# SECUREBRD_003.net
KiCad netlist of a schematic drawn in EAGLE
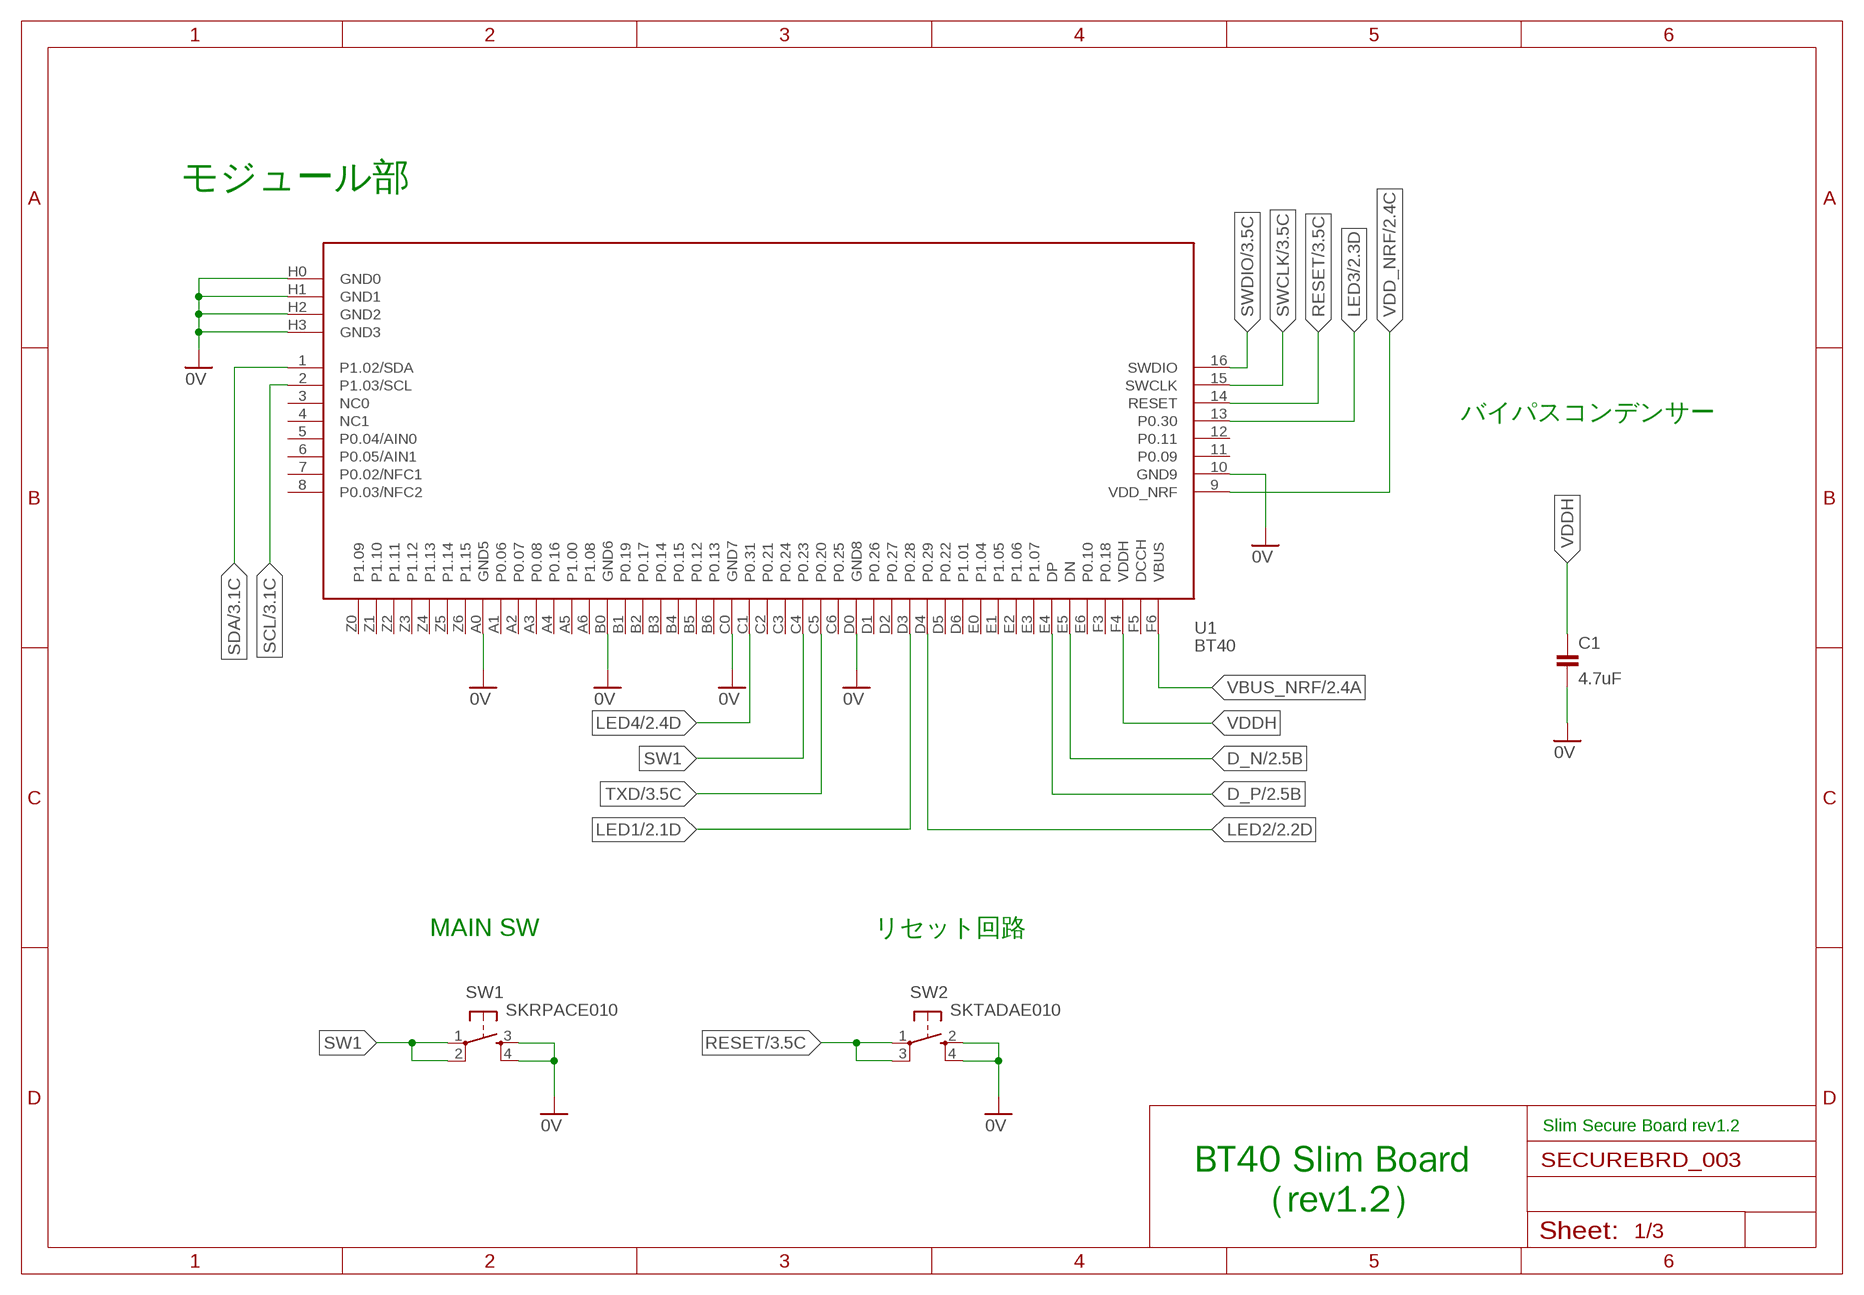
[diagram p0: schematic, sheet 1]
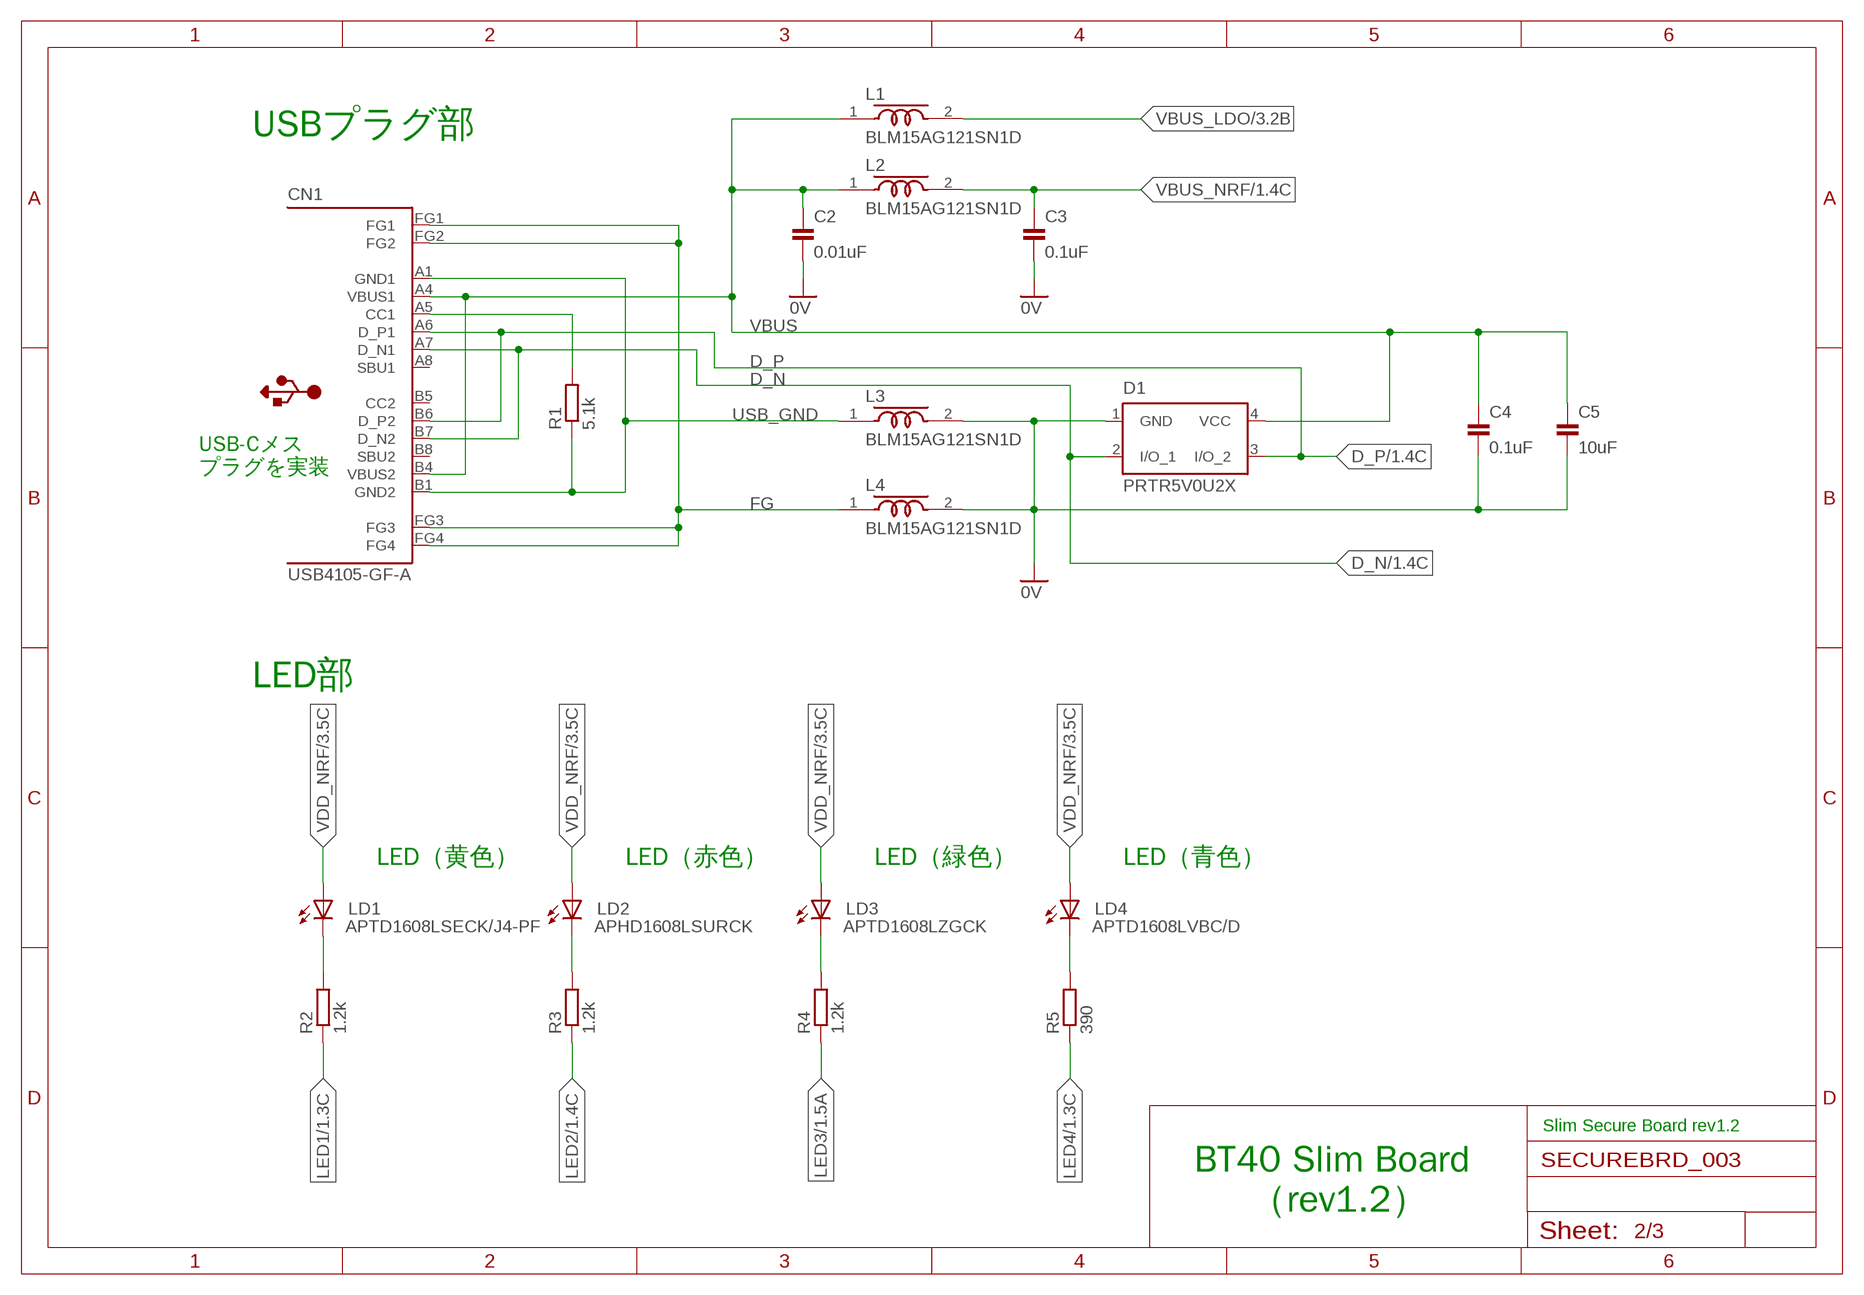
[diagram p1: schematic, sheet 2]
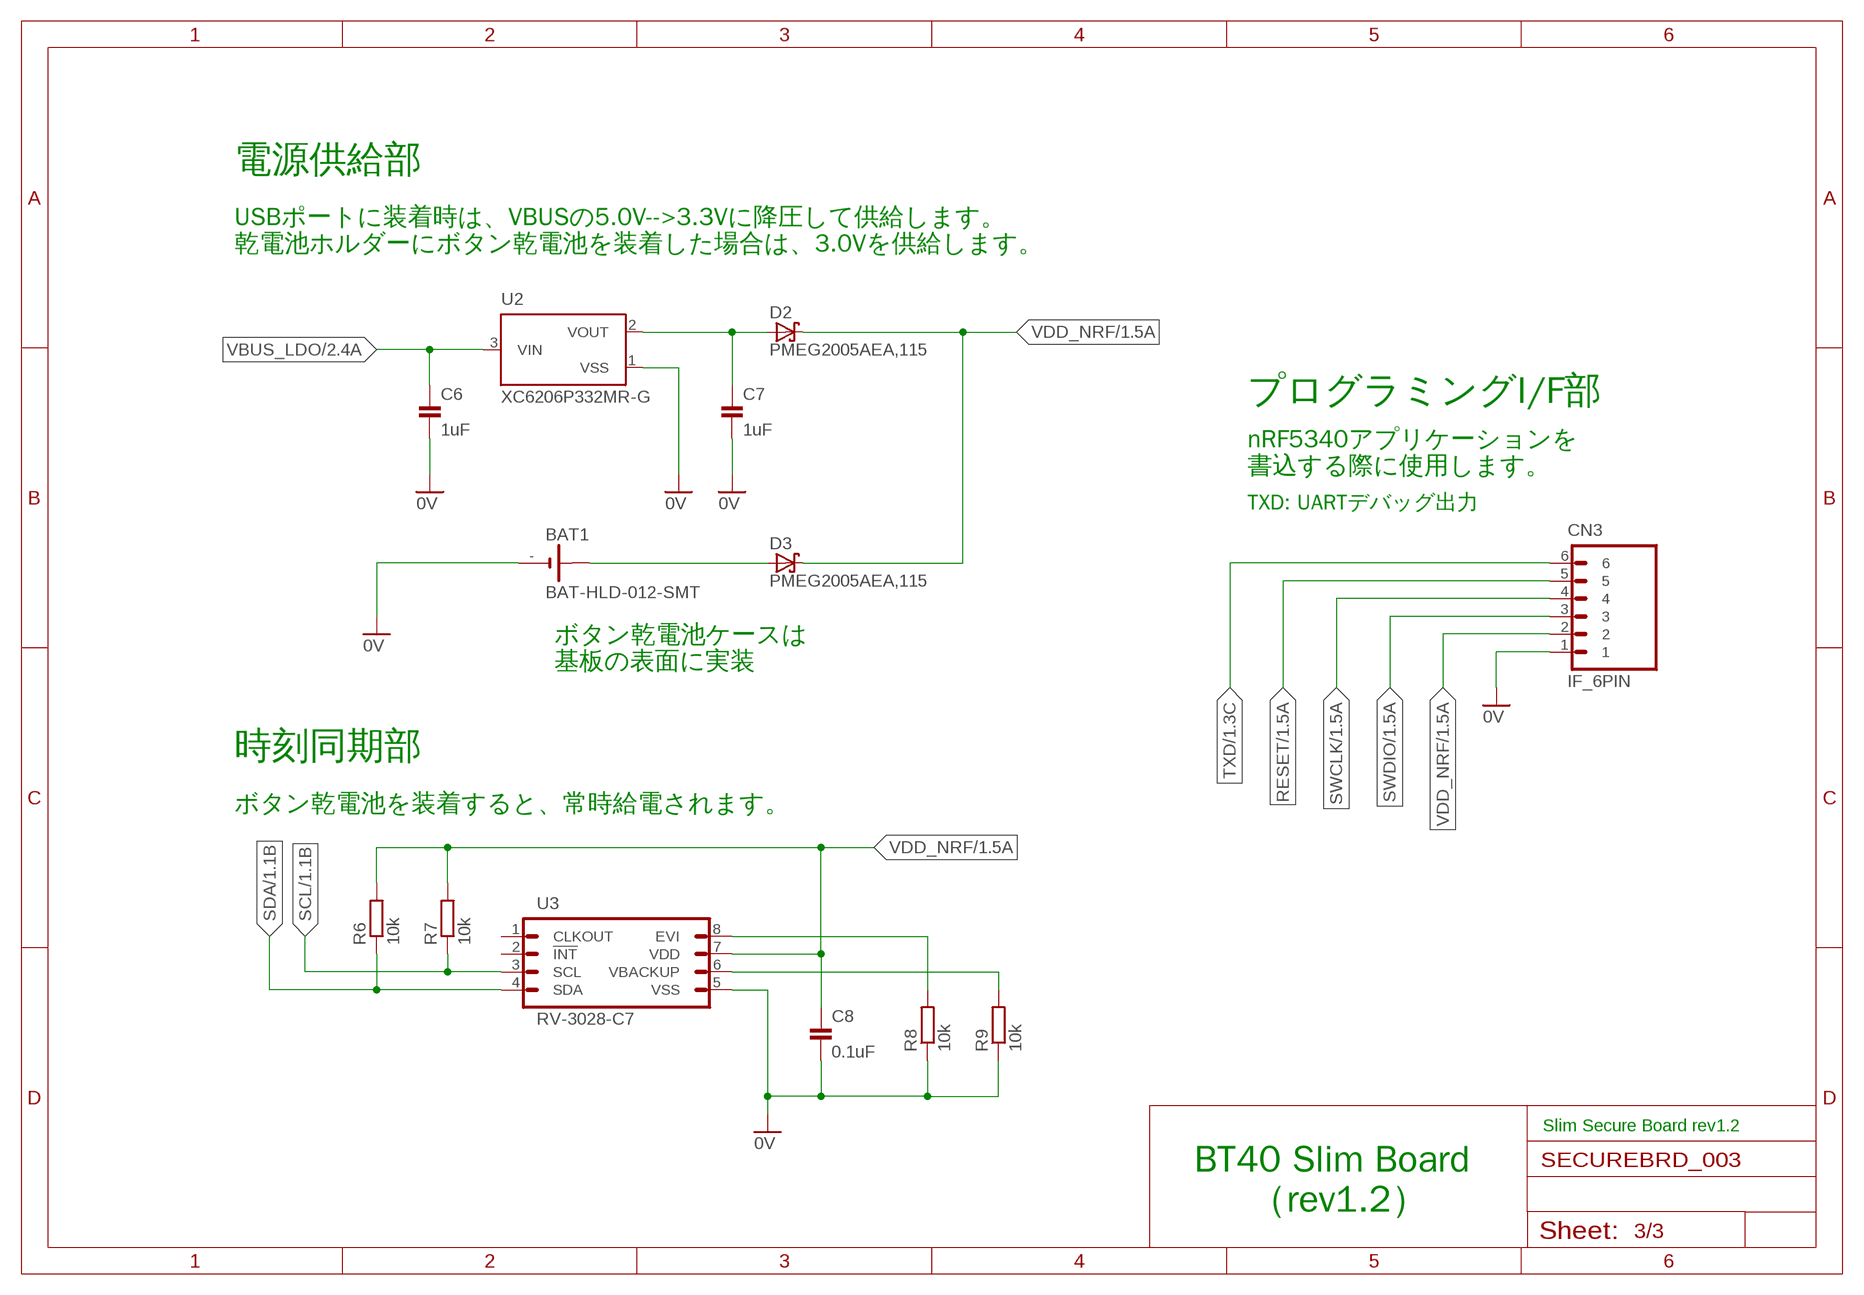
[diagram p2: schematic, sheet 3]

(export (version "E")
  (design (tool "Eeschema 10.0.6"))
  (components
    (comp (ref "BAT1")
      (value "BAT-HLD-012-SMT")
      (footprint "eagle-import:BAT-HLD-012-SMT")
      (libsource (lib "eagle-import") (part "BAT-HLD-012-SMT"))
    )
    (comp (ref "C6")
      (value "1uF")
      (footprint "eagle-import:C0603K")
      (libsource (lib "eagle-import") (part "CAP_0603"))
    )
    (comp (ref "C7")
      (value "1uF")
      (footprint "eagle-import:C0603K")
      (libsource (lib "eagle-import") (part "CAP_0603"))
    )
    (comp (ref "C8")
      (value "0.1uF")
      (footprint "eagle-import:C0402K")
      (libsource (lib "eagle-import") (part "CAP_0402K"))
    )
    (comp (ref "CN3")
      (value "IF_6PIN")
      (footprint "eagle-import:HEADER_6PIN")
      (libsource (lib "eagle-import") (part "IF_6PIN"))
    )
    (comp (ref "D2")
      (value "PMEG2005AEA,115")
      (footprint "eagle-import:SOD323-W")
      (libsource (lib "eagle-import") (part "PMEG2005AEA,115"))
    )
    (comp (ref "D3")
      (value "PMEG2005AEA,115")
      (footprint "eagle-import:SOD323-W")
      (libsource (lib "eagle-import") (part "PMEG2005AEA,115"))
    )
    (comp (ref "R6")
      (value "10k")
      (footprint "eagle-import:R0402")
      (libsource (lib "eagle-import") (part "RESISTOR_0402"))
    )
    (comp (ref "R7")
      (value "10k")
      (footprint "eagle-import:R0402")
      (libsource (lib "eagle-import") (part "RESISTOR_0402"))
    )
    (comp (ref "R8")
      (value "10k")
      (footprint "eagle-import:R0402")
      (libsource (lib "eagle-import") (part "RESISTOR_0402"))
    )
    (comp (ref "R9")
      (value "10k")
      (footprint "eagle-import:R0402")
      (libsource (lib "eagle-import") (part "RESISTOR_0402"))
    )
    (comp (ref "U2")
      (value "XC6206P332MR-G")
      (footprint "eagle-import:SOT23")
      (libsource (lib "eagle-import") (part "XC6206P332MR-G"))
    )
    (comp (ref "U3")
      (value "RV-3028-C7")
      (footprint "eagle-import:SON-8")
      (libsource (lib "eagle-import") (part "RV-3028-C7"))
    )
    (comp (ref "C2")
      (value "0.01uF")
      (footprint "eagle-import:C0402K")
      (libsource (lib "eagle-import") (part "CAP_0402K"))
    )
    (comp (ref "C3")
      (value "0.1uF")
      (footprint "eagle-import:C0402K")
      (libsource (lib "eagle-import") (part "CAP_0402K"))
    )
    (comp (ref "C4")
      (value "0.1uF")
      (footprint "eagle-import:C0402K")
      (libsource (lib "eagle-import") (part "CAP_0402K"))
    )
    (comp (ref "C5")
      (value "10uF")
      (footprint "eagle-import:C0603K")
      (libsource (lib "eagle-import") (part "CAP_0603"))
    )
    (comp (ref "CN1")
      (value "USB4105-GF-A")
      (footprint "eagle-import:USB4105-GF-A")
      (libsource (lib "eagle-import") (part "USB4105-GF-A"))
    )
    (comp (ref "D1")
      (value "PRTR5V0U2X")
      (footprint "eagle-import:SOT143B")
      (libsource (lib "eagle-import") (part "PRTR5V0U2X"))
    )
    (comp (ref "L1")
      (value "BLM15AG121SN1D")
      (footprint "eagle-import:C0402K")
      (libsource (lib "eagle-import") (part "BLM15AG121SN1D"))
    )
    (comp (ref "L2")
      (value "BLM15AG121SN1D")
      (footprint "eagle-import:C0402K")
      (libsource (lib "eagle-import") (part "BLM15AG121SN1D"))
    )
    (comp (ref "L3")
      (value "BLM15AG121SN1D")
      (footprint "eagle-import:C0402K")
      (libsource (lib "eagle-import") (part "BLM15AG121SN1D"))
    )
    (comp (ref "L4")
      (value "BLM15AG121SN1D")
      (footprint "eagle-import:C0402K")
      (libsource (lib "eagle-import") (part "BLM15AG121SN1D"))
    )
    (comp (ref "LD1")
      (value "APTD1608LSECK/J4-PF")
      (footprint "eagle-import:APTD1608")
      (libsource (lib "eagle-import") (part "APTD1608LSECK/J4-PF"))
    )
    (comp (ref "LD2")
      (value "APHD1608LSURCK")
      (footprint "eagle-import:APTD1608")
      (libsource (lib "eagle-import") (part "APHD1608LSURCK"))
    )
    (comp (ref "LD3")
      (value "APTD1608LZGCK")
      (footprint "eagle-import:APTD1608")
      (libsource (lib "eagle-import") (part "APTD1608LZGCK"))
    )
    (comp (ref "LD4")
      (value "APTD1608LVBC/D")
      (footprint "eagle-import:APTD1608")
      (libsource (lib "eagle-import") (part "APTD1608LVBC/D"))
    )
    (comp (ref "R1")
      (value "5.1k")
      (footprint "eagle-import:R0402")
      (libsource (lib "eagle-import") (part "RESISTOR_0402"))
    )
    (comp (ref "R2")
      (value "1.2k")
      (footprint "eagle-import:R0402")
      (libsource (lib "eagle-import") (part "RESISTOR_0402"))
    )
    (comp (ref "R3")
      (value "1.2k")
      (footprint "eagle-import:R0402")
      (libsource (lib "eagle-import") (part "RESISTOR_0402"))
    )
    (comp (ref "R4")
      (value "1.2k")
      (footprint "eagle-import:R0402")
      (libsource (lib "eagle-import") (part "RESISTOR_0402"))
    )
    (comp (ref "R5")
      (value "390")
      (footprint "eagle-import:R0402")
      (libsource (lib "eagle-import") (part "RESISTOR_0402"))
    )
    (comp (ref "C1")
      (value "4.7uF")
      (footprint "eagle-import:C0603K")
      (libsource (lib "eagle-import") (part "CAP_0603"))
    )
    (comp (ref "SW1")
      (value "SKRPACE010")
      (footprint "eagle-import:SKRPACE010")
      (libsource (lib "eagle-import") (part "SKRPACE010"))
    )
    (comp (ref "SW2")
      (value "SKTADAE010")
      (footprint "eagle-import:SKTADAE010")
      (libsource (lib "eagle-import") (part "SKTADAE010"))
    )
    (comp (ref "U1")
      (value "BT40")
      (footprint "eagle-import:BM40-B_1PRIMARY")
      (libsource (lib "eagle-import") (part "BT40"))
    )
  )
  (nets
    (net (code "1") (name "0V") (class "Default")
      (node (ref "BAT1") (pin "-") (pinfunction "-_-") (pintype "passive"))
      (node (ref "C1") (pin "2") (pinfunction "2_2") (pintype "passive"))
      (node (ref "C2") (pin "2") (pinfunction "2_2") (pintype "passive"))
      (node (ref "C3") (pin "2") (pinfunction "2_2") (pintype "passive"))
      (node (ref "C4") (pin "2") (pinfunction "2_2") (pintype "passive"))
      (node (ref "C5") (pin "2") (pinfunction "2_2") (pintype "passive"))
      (node (ref "C6") (pin "2") (pinfunction "2_2") (pintype "passive"))
      (node (ref "C7") (pin "2") (pinfunction "2_2") (pintype "passive"))
      (node (ref "C8") (pin "2") (pinfunction "2_2") (pintype "passive"))
      (node (ref "CN3") (pin "1") (pinfunction "1_1") (pintype "passive"))
      (node (ref "D1") (pin "1") (pinfunction "GND_1") (pintype "passive"))
      (node (ref "L3") (pin "2") (pinfunction "2_2") (pintype "passive"))
      (node (ref "L4") (pin "2") (pinfunction "2_2") (pintype "passive"))
      (node (ref "R8") (pin "1") (pinfunction "1_1") (pintype "passive"))
      (node (ref "R9") (pin "1") (pinfunction "1_1") (pintype "passive"))
      (node (ref "SW1") (pin "3") (pinfunction "S_3") (pintype "passive"))
      (node (ref "SW1") (pin "4") (pinfunction "S1_4") (pintype "passive"))
      (node (ref "SW2") (pin "2") (pinfunction "S_2") (pintype "passive"))
      (node (ref "SW2") (pin "4") (pinfunction "S1_4") (pintype "passive"))
      (node (ref "U1") (pin "10") (pinfunction "GND9_10") (pintype "passive"))
      (node (ref "U1") (pin "A0") (pinfunction "GND5_A0") (pintype "passive"))
      (node (ref "U1") (pin "B0") (pinfunction "GND6_B0") (pintype "passive"))
      (node (ref "U1") (pin "C0") (pinfunction "GND7_C0") (pintype "passive"))
      (node (ref "U1") (pin "D0") (pinfunction "GND8_D0") (pintype "passive"))
      (node (ref "U1") (pin "H0") (pinfunction "GND0_H0") (pintype "passive"))
      (node (ref "U1") (pin "H1") (pinfunction "GND1_H1") (pintype "passive"))
      (node (ref "U1") (pin "H2") (pinfunction "GND2_H2") (pintype "passive"))
      (node (ref "U1") (pin "H3") (pinfunction "GND3_H3") (pintype "passive"))
      (node (ref "U2") (pin "1") (pinfunction "VSS_1") (pintype "passive"))
      (node (ref "U3") (pin "5") (pinfunction "VSS_5") (pintype "passive"))
    )
    (net (code "2") (name "D_N") (class "Default")
      (node (ref "CN1") (pin "A7") (pinfunction "D_N1_A7") (pintype "bidirectional"))
      (node (ref "CN1") (pin "B7") (pinfunction "D_N2_B7") (pintype "bidirectional"))
      (node (ref "D1") (pin "2") (pinfunction "I/O_1_2") (pintype "bidirectional"))
      (node (ref "U1") (pin "E5") (pinfunction "DN_E5") (pintype "bidirectional"))
    )
    (net (code "3") (name "D_P") (class "Default")
      (node (ref "CN1") (pin "A6") (pinfunction "D_P1_A6") (pintype "bidirectional"))
      (node (ref "CN1") (pin "B6") (pinfunction "D_P2_B6") (pintype "bidirectional"))
      (node (ref "D1") (pin "3") (pinfunction "I/O_2_3") (pintype "bidirectional"))
      (node (ref "U1") (pin "E4") (pinfunction "DP_E4") (pintype "bidirectional"))
    )
    (net (code "4") (name "FG") (class "Default")
      (node (ref "CN1") (pin "FG1") (pinfunction "FG1_FG1") (pintype "passive"))
      (node (ref "CN1") (pin "FG2") (pinfunction "FG2_FG2") (pintype "bidirectional"))
      (node (ref "CN1") (pin "FG3") (pinfunction "FG3_FG3") (pintype "passive"))
      (node (ref "CN1") (pin "FG4") (pinfunction "FG4_FG4") (pintype "passive"))
      (node (ref "L4") (pin "1") (pinfunction "1_1") (pintype "passive"))
    )
    (net (code "5") (name "LED1") (class "Default")
      (node (ref "R2") (pin "1") (pinfunction "1_1") (pintype "passive"))
      (node (ref "U1") (pin "D3") (pinfunction "P0.28_D3") (pintype "bidirectional"))
    )
    (net (code "6") (name "LED2") (class "Default")
      (node (ref "R3") (pin "1") (pinfunction "1_1") (pintype "passive"))
      (node (ref "U1") (pin "D4") (pinfunction "P0.29_D4") (pintype "bidirectional"))
    )
    (net (code "7") (name "LED3") (class "Default")
      (node (ref "R4") (pin "1") (pinfunction "1_1") (pintype "passive"))
      (node (ref "U1") (pin "13") (pinfunction "P0.30_13") (pintype "bidirectional"))
    )
    (net (code "8") (name "LED4") (class "Default")
      (node (ref "R5") (pin "1") (pinfunction "1_1") (pintype "passive"))
      (node (ref "U1") (pin "C1") (pinfunction "P0.31_C1") (pintype "bidirectional"))
    )
    (net (code "9") (name "Net-(BAT1-+)") (class "Default")
      (node (ref "BAT1") (pin "+@2") (pinfunction "+_+@2") (pintype "passive"))
      (node (ref "D3") (pin "A") (pinfunction "A_A") (pintype "passive"))
    )
    (net (code "10") (name "Net-(CN1-CC1)") (class "Default")
      (node (ref "CN1") (pin "A5") (pinfunction "CC1_A5") (pintype "passive"))
      (node (ref "R1") (pin "2") (pinfunction "2_2") (pintype "passive"))
    )
    (net (code "11") (name "Net-(LD1-PadC)") (class "Default")
      (node (ref "LD1") (pin "C") (pinfunction "C_C") (pintype "passive"))
      (node (ref "R2") (pin "2") (pinfunction "2_2") (pintype "passive"))
    )
    (net (code "12") (name "Net-(LD2-PadC)") (class "Default")
      (node (ref "LD2") (pin "C") (pinfunction "C_C") (pintype "passive"))
      (node (ref "R3") (pin "2") (pinfunction "2_2") (pintype "passive"))
    )
    (net (code "13") (name "Net-(LD3-PadC)") (class "Default")
      (node (ref "LD3") (pin "C") (pinfunction "C_C") (pintype "passive"))
      (node (ref "R4") (pin "2") (pinfunction "2_2") (pintype "passive"))
    )
    (net (code "14") (name "Net-(LD4-PadC)") (class "Default")
      (node (ref "LD4") (pin "C") (pinfunction "C_C") (pintype "passive"))
      (node (ref "R5") (pin "2") (pinfunction "2_2") (pintype "passive"))
    )
    (net (code "15") (name "Net-(U2-VOUT)") (class "Default")
      (node (ref "C7") (pin "1") (pinfunction "1_1") (pintype "passive"))
      (node (ref "D2") (pin "A") (pinfunction "A_A") (pintype "passive"))
      (node (ref "U2") (pin "2") (pinfunction "VOUT_2") (pintype "passive"))
    )
    (net (code "16") (name "Net-(U3-EVI)") (class "Default")
      (node (ref "R8") (pin "2") (pinfunction "2_2") (pintype "passive"))
      (node (ref "U3") (pin "8") (pinfunction "EVI_8") (pintype "bidirectional"))
    )
    (net (code "17") (name "Net-(U3-VBACKUP)") (class "Default")
      (node (ref "R9") (pin "2") (pinfunction "2_2") (pintype "passive"))
      (node (ref "U3") (pin "6") (pinfunction "VBACKUP_6") (pintype "passive"))
    )
    (net (code "18") (name "RESET") (class "Default")
      (node (ref "CN3") (pin "5") (pinfunction "5_5") (pintype "passive"))
      (node (ref "SW2") (pin "1") (pinfunction "P_1") (pintype "passive"))
      (node (ref "SW2") (pin "3") (pinfunction "P1_3") (pintype "passive"))
      (node (ref "U1") (pin "14") (pinfunction "RESET_14") (pintype "bidirectional"))
    )
    (net (code "19") (name "SCL") (class "Default")
      (node (ref "R7") (pin "1") (pinfunction "1_1") (pintype "passive"))
      (node (ref "U1") (pin "2") (pinfunction "P1.03/SCL_2") (pintype "bidirectional"))
      (node (ref "U3") (pin "3") (pinfunction "SCL_3") (pintype "bidirectional"))
    )
    (net (code "20") (name "SDA") (class "Default")
      (node (ref "R6") (pin "1") (pinfunction "1_1") (pintype "passive"))
      (node (ref "U1") (pin "1") (pinfunction "P1.02/SDA_1") (pintype "bidirectional"))
      (node (ref "U3") (pin "4") (pinfunction "SDA_4") (pintype "bidirectional"))
    )
    (net (code "21") (name "SW1") (class "Default")
      (node (ref "SW1") (pin "1") (pinfunction "P_1") (pintype "passive"))
      (node (ref "SW1") (pin "2") (pinfunction "P1_2") (pintype "passive"))
      (node (ref "U1") (pin "C4") (pinfunction "P0.23_C4") (pintype "bidirectional"))
    )
    (net (code "22") (name "SWCLK") (class "Default")
      (node (ref "CN3") (pin "4") (pinfunction "4_4") (pintype "passive"))
      (node (ref "U1") (pin "15") (pinfunction "SWCLK_15") (pintype "bidirectional"))
    )
    (net (code "23") (name "SWDIO") (class "Default")
      (node (ref "CN3") (pin "3") (pinfunction "3_3") (pintype "passive"))
      (node (ref "U1") (pin "16") (pinfunction "SWDIO_16") (pintype "bidirectional"))
    )
    (net (code "24") (name "TXD") (class "Default")
      (node (ref "CN3") (pin "6") (pinfunction "6_6") (pintype "passive"))
      (node (ref "U1") (pin "C5") (pinfunction "P0.20_C5") (pintype "bidirectional"))
    )
    (net (code "25") (name "USB_GND") (class "Default")
      (node (ref "CN1") (pin "A1") (pinfunction "GND1_A1") (pintype "passive"))
      (node (ref "CN1") (pin "B1") (pinfunction "GND2_B1") (pintype "passive"))
      (node (ref "L3") (pin "1") (pinfunction "1_1") (pintype "passive"))
      (node (ref "R1") (pin "1") (pinfunction "1_1") (pintype "passive"))
    )
    (net (code "26") (name "VBUS") (class "Default")
      (node (ref "C2") (pin "1") (pinfunction "1_1") (pintype "passive"))
      (node (ref "C4") (pin "1") (pinfunction "1_1") (pintype "passive"))
      (node (ref "C5") (pin "1") (pinfunction "1_1") (pintype "passive"))
      (node (ref "CN1") (pin "A4") (pinfunction "VBUS1_A4") (pintype "passive"))
      (node (ref "CN1") (pin "B4") (pinfunction "VBUS2_B4") (pintype "passive"))
      (node (ref "D1") (pin "4") (pinfunction "VCC_4") (pintype "passive"))
      (node (ref "L1") (pin "1") (pinfunction "1_1") (pintype "passive"))
      (node (ref "L2") (pin "1") (pinfunction "1_1") (pintype "passive"))
    )
    (net (code "27") (name "VBUS_LDO") (class "Default")
      (node (ref "C6") (pin "1") (pinfunction "1_1") (pintype "passive"))
      (node (ref "L1") (pin "2") (pinfunction "2_2") (pintype "passive"))
      (node (ref "U2") (pin "3") (pinfunction "VIN_3") (pintype "passive"))
    )
    (net (code "28") (name "VBUS_NRF") (class "Default")
      (node (ref "C3") (pin "1") (pinfunction "1_1") (pintype "passive"))
      (node (ref "L2") (pin "2") (pinfunction "2_2") (pintype "passive"))
      (node (ref "U1") (pin "F6") (pinfunction "VBUS_F6") (pintype "passive"))
    )
    (net (code "29") (name "VDDH") (class "Default")
      (node (ref "C1") (pin "1") (pinfunction "1_1") (pintype "passive"))
      (node (ref "U1") (pin "F4") (pinfunction "VDDH_F4") (pintype "passive"))
    )
    (net (code "30") (name "VDD_NRF") (class "Default")
      (node (ref "C8") (pin "1") (pinfunction "1_1") (pintype "passive"))
      (node (ref "CN3") (pin "2") (pinfunction "2_2") (pintype "passive"))
      (node (ref "D2") (pin "C") (pinfunction "C_C") (pintype "passive"))
      (node (ref "D3") (pin "C") (pinfunction "C_C") (pintype "passive"))
      (node (ref "LD1") (pin "A") (pinfunction "A_A") (pintype "passive"))
      (node (ref "LD2") (pin "A") (pinfunction "A_A") (pintype "passive"))
      (node (ref "LD3") (pin "A") (pinfunction "A_A") (pintype "passive"))
      (node (ref "LD4") (pin "A") (pinfunction "A_A") (pintype "passive"))
      (node (ref "R6") (pin "2") (pinfunction "2_2") (pintype "passive"))
      (node (ref "R7") (pin "2") (pinfunction "2_2") (pintype "passive"))
      (node (ref "U1") (pin "9") (pinfunction "VDD_NRF_9") (pintype "passive"))
      (node (ref "U3") (pin "7") (pinfunction "VDD_7") (pintype "passive"))
    )
    (net (code "31") (name "unconnected-(CN1-CC2-PadB5)") (class "Default")
      (node (ref "CN1") (pin "B5") (pinfunction "CC2_B5") (pintype "passive"))
    )
    (net (code "32") (name "unconnected-(CN1-SBU1-PadA8)") (class "Default")
      (node (ref "CN1") (pin "A8") (pinfunction "SBU1_A8") (pintype "passive"))
    )
    (net (code "33") (name "unconnected-(CN1-SBU2-PadB8)") (class "Default")
      (node (ref "CN1") (pin "B8") (pinfunction "SBU2_B8") (pintype "passive"))
    )
    (net (code "34") (name "unconnected-(U1-DCCH-PadF5)") (class "Default")
      (node (ref "U1") (pin "F5") (pinfunction "DCCH_F5") (pintype "passive"))
    )
    (net (code "35") (name "unconnected-(U1-NC0-Pad3)") (class "Default")
      (node (ref "U1") (pin "3") (pinfunction "NC0_3") (pintype "no_connect"))
    )
    (net (code "36") (name "unconnected-(U1-NC1-Pad4)") (class "Default")
      (node (ref "U1") (pin "4") (pinfunction "NC1_4") (pintype "no_connect"))
    )
    (net (code "37") (name "unconnected-(U1-P0.02{slash}NFC1-Pad7)") (class "Default")
      (node (ref "U1") (pin "7") (pinfunction "P0.02/NFC1_7") (pintype "bidirectional"))
    )
    (net (code "38") (name "unconnected-(U1-P0.03{slash}NFC2-Pad8)") (class "Default")
      (node (ref "U1") (pin "8") (pinfunction "P0.03/NFC2_8") (pintype "bidirectional"))
    )
    (net (code "39") (name "unconnected-(U1-P0.04{slash}AIN0-Pad5)") (class "Default")
      (node (ref "U1") (pin "5") (pinfunction "P0.04/AIN0_5") (pintype "bidirectional"))
    )
    (net (code "40") (name "unconnected-(U1-P0.05{slash}AIN1-Pad6)") (class "Default")
      (node (ref "U1") (pin "6") (pinfunction "P0.05/AIN1_6") (pintype "bidirectional"))
    )
    (net (code "41") (name "unconnected-(U1-P0.06-PadA1)") (class "Default")
      (node (ref "U1") (pin "A1") (pinfunction "P0.06_A1") (pintype "bidirectional"))
    )
    (net (code "42") (name "unconnected-(U1-P0.07-PadA2)") (class "Default")
      (node (ref "U1") (pin "A2") (pinfunction "P0.07_A2") (pintype "bidirectional"))
    )
    (net (code "43") (name "unconnected-(U1-P0.08-PadA3)") (class "Default")
      (node (ref "U1") (pin "A3") (pinfunction "P0.08_A3") (pintype "bidirectional"))
    )
    (net (code "44") (name "unconnected-(U1-P0.09-Pad11)") (class "Default")
      (node (ref "U1") (pin "11") (pinfunction "P0.09_11") (pintype "bidirectional"))
    )
    (net (code "45") (name "unconnected-(U1-P0.10-PadE6)") (class "Default")
      (node (ref "U1") (pin "E6") (pinfunction "P0.10_E6") (pintype "bidirectional"))
    )
    (net (code "46") (name "unconnected-(U1-P0.11-Pad12)") (class "Default")
      (node (ref "U1") (pin "12") (pinfunction "P0.11_12") (pintype "bidirectional"))
    )
    (net (code "47") (name "unconnected-(U1-P0.12-PadB5)") (class "Default")
      (node (ref "U1") (pin "B5") (pinfunction "P0.12_B5") (pintype "bidirectional"))
    )
    (net (code "48") (name "unconnected-(U1-P0.13-PadB6)") (class "Default")
      (node (ref "U1") (pin "B6") (pinfunction "P0.13_B6") (pintype "bidirectional"))
    )
    (net (code "49") (name "unconnected-(U1-P0.14-PadB3)") (class "Default")
      (node (ref "U1") (pin "B3") (pinfunction "P0.14_B3") (pintype "bidirectional"))
    )
    (net (code "50") (name "unconnected-(U1-P0.15-PadB4)") (class "Default")
      (node (ref "U1") (pin "B4") (pinfunction "P0.15_B4") (pintype "bidirectional"))
    )
    (net (code "51") (name "unconnected-(U1-P0.16-PadA4)") (class "Default")
      (node (ref "U1") (pin "A4") (pinfunction "P0.16_A4") (pintype "bidirectional"))
    )
    (net (code "52") (name "unconnected-(U1-P0.17-PadB2)") (class "Default")
      (node (ref "U1") (pin "B2") (pinfunction "P0.17_B2") (pintype "bidirectional"))
    )
    (net (code "53") (name "unconnected-(U1-P0.18-PadF3)") (class "Default")
      (node (ref "U1") (pin "F3") (pinfunction "P0.18_F3") (pintype "bidirectional"))
    )
    (net (code "54") (name "unconnected-(U1-P0.19-PadB1)") (class "Default")
      (node (ref "U1") (pin "B1") (pinfunction "P0.19_B1") (pintype "bidirectional"))
    )
    (net (code "55") (name "unconnected-(U1-P0.21-PadC2)") (class "Default")
      (node (ref "U1") (pin "C2") (pinfunction "P0.21_C2") (pintype "bidirectional"))
    )
    (net (code "56") (name "unconnected-(U1-P0.22-PadD5)") (class "Default")
      (node (ref "U1") (pin "D5") (pinfunction "P0.22_D5") (pintype "bidirectional"))
    )
    (net (code "57") (name "unconnected-(U1-P0.24-PadC3)") (class "Default")
      (node (ref "U1") (pin "C3") (pinfunction "P0.24_C3") (pintype "bidirectional"))
    )
    (net (code "58") (name "unconnected-(U1-P0.25-PadC6)") (class "Default")
      (node (ref "U1") (pin "C6") (pinfunction "P0.25_C6") (pintype "bidirectional"))
    )
    (net (code "59") (name "unconnected-(U1-P0.26-PadD1)") (class "Default")
      (node (ref "U1") (pin "D1") (pinfunction "P0.26_D1") (pintype "bidirectional"))
    )
    (net (code "60") (name "unconnected-(U1-P0.27-PadD2)") (class "Default")
      (node (ref "U1") (pin "D2") (pinfunction "P0.27_D2") (pintype "bidirectional"))
    )
    (net (code "61") (name "unconnected-(U1-P1.00-PadA5)") (class "Default")
      (node (ref "U1") (pin "A5") (pinfunction "P1.00_A5") (pintype "bidirectional"))
    )
    (net (code "62") (name "unconnected-(U1-P1.01-PadD6)") (class "Default")
      (node (ref "U1") (pin "D6") (pinfunction "P1.01_D6") (pintype "bidirectional"))
    )
    (net (code "63") (name "unconnected-(U1-P1.04-PadE0)") (class "Default")
      (node (ref "U1") (pin "E0") (pinfunction "P1.04_E0") (pintype "bidirectional"))
    )
    (net (code "64") (name "unconnected-(U1-P1.05-PadE1)") (class "Default")
      (node (ref "U1") (pin "E1") (pinfunction "P1.05_E1") (pintype "bidirectional"))
    )
    (net (code "65") (name "unconnected-(U1-P1.06-PadE2)") (class "Default")
      (node (ref "U1") (pin "E2") (pinfunction "P1.06_E2") (pintype "bidirectional"))
    )
    (net (code "66") (name "unconnected-(U1-P1.07-PadE3)") (class "Default")
      (node (ref "U1") (pin "E3") (pinfunction "P1.07_E3") (pintype "bidirectional"))
    )
    (net (code "67") (name "unconnected-(U1-P1.08-PadA6)") (class "Default")
      (node (ref "U1") (pin "A6") (pinfunction "P1.08_A6") (pintype "bidirectional"))
    )
    (net (code "68") (name "unconnected-(U1-P1.09-PadZ0)") (class "Default")
      (node (ref "U1") (pin "Z0") (pinfunction "P1.09_Z0") (pintype "bidirectional"))
    )
    (net (code "69") (name "unconnected-(U1-P1.10-PadZ1)") (class "Default")
      (node (ref "U1") (pin "Z1") (pinfunction "P1.10_Z1") (pintype "bidirectional"))
    )
    (net (code "70") (name "unconnected-(U1-P1.11-PadZ2)") (class "Default")
      (node (ref "U1") (pin "Z2") (pinfunction "P1.11_Z2") (pintype "bidirectional"))
    )
    (net (code "71") (name "unconnected-(U1-P1.12-PadZ3)") (class "Default")
      (node (ref "U1") (pin "Z3") (pinfunction "P1.12_Z3") (pintype "bidirectional"))
    )
    (net (code "72") (name "unconnected-(U1-P1.13-PadZ4)") (class "Default")
      (node (ref "U1") (pin "Z4") (pinfunction "P1.13_Z4") (pintype "bidirectional"))
    )
    (net (code "73") (name "unconnected-(U1-P1.14-PadZ5)") (class "Default")
      (node (ref "U1") (pin "Z5") (pinfunction "P1.14_Z5") (pintype "bidirectional"))
    )
    (net (code "74") (name "unconnected-(U1-P1.15-PadZ6)") (class "Default")
      (node (ref "U1") (pin "Z6") (pinfunction "P1.15_Z6") (pintype "bidirectional"))
    )
    (net (code "75") (name "unconnected-(U3-CLKOUT-Pad1)") (class "Default")
      (node (ref "U3") (pin "1") (pinfunction "CLKOUT_1") (pintype "bidirectional"))
    )
    (net (code "76") (name "unconnected-(U3-~{INT}-Pad2)") (class "Default")
      (node (ref "U3") (pin "2") (pinfunction "~{INT}_2") (pintype "bidirectional"))
    )
  )
)
